# motor_drive.net
KiCad netlist of a schematic drawn in Altium Designer
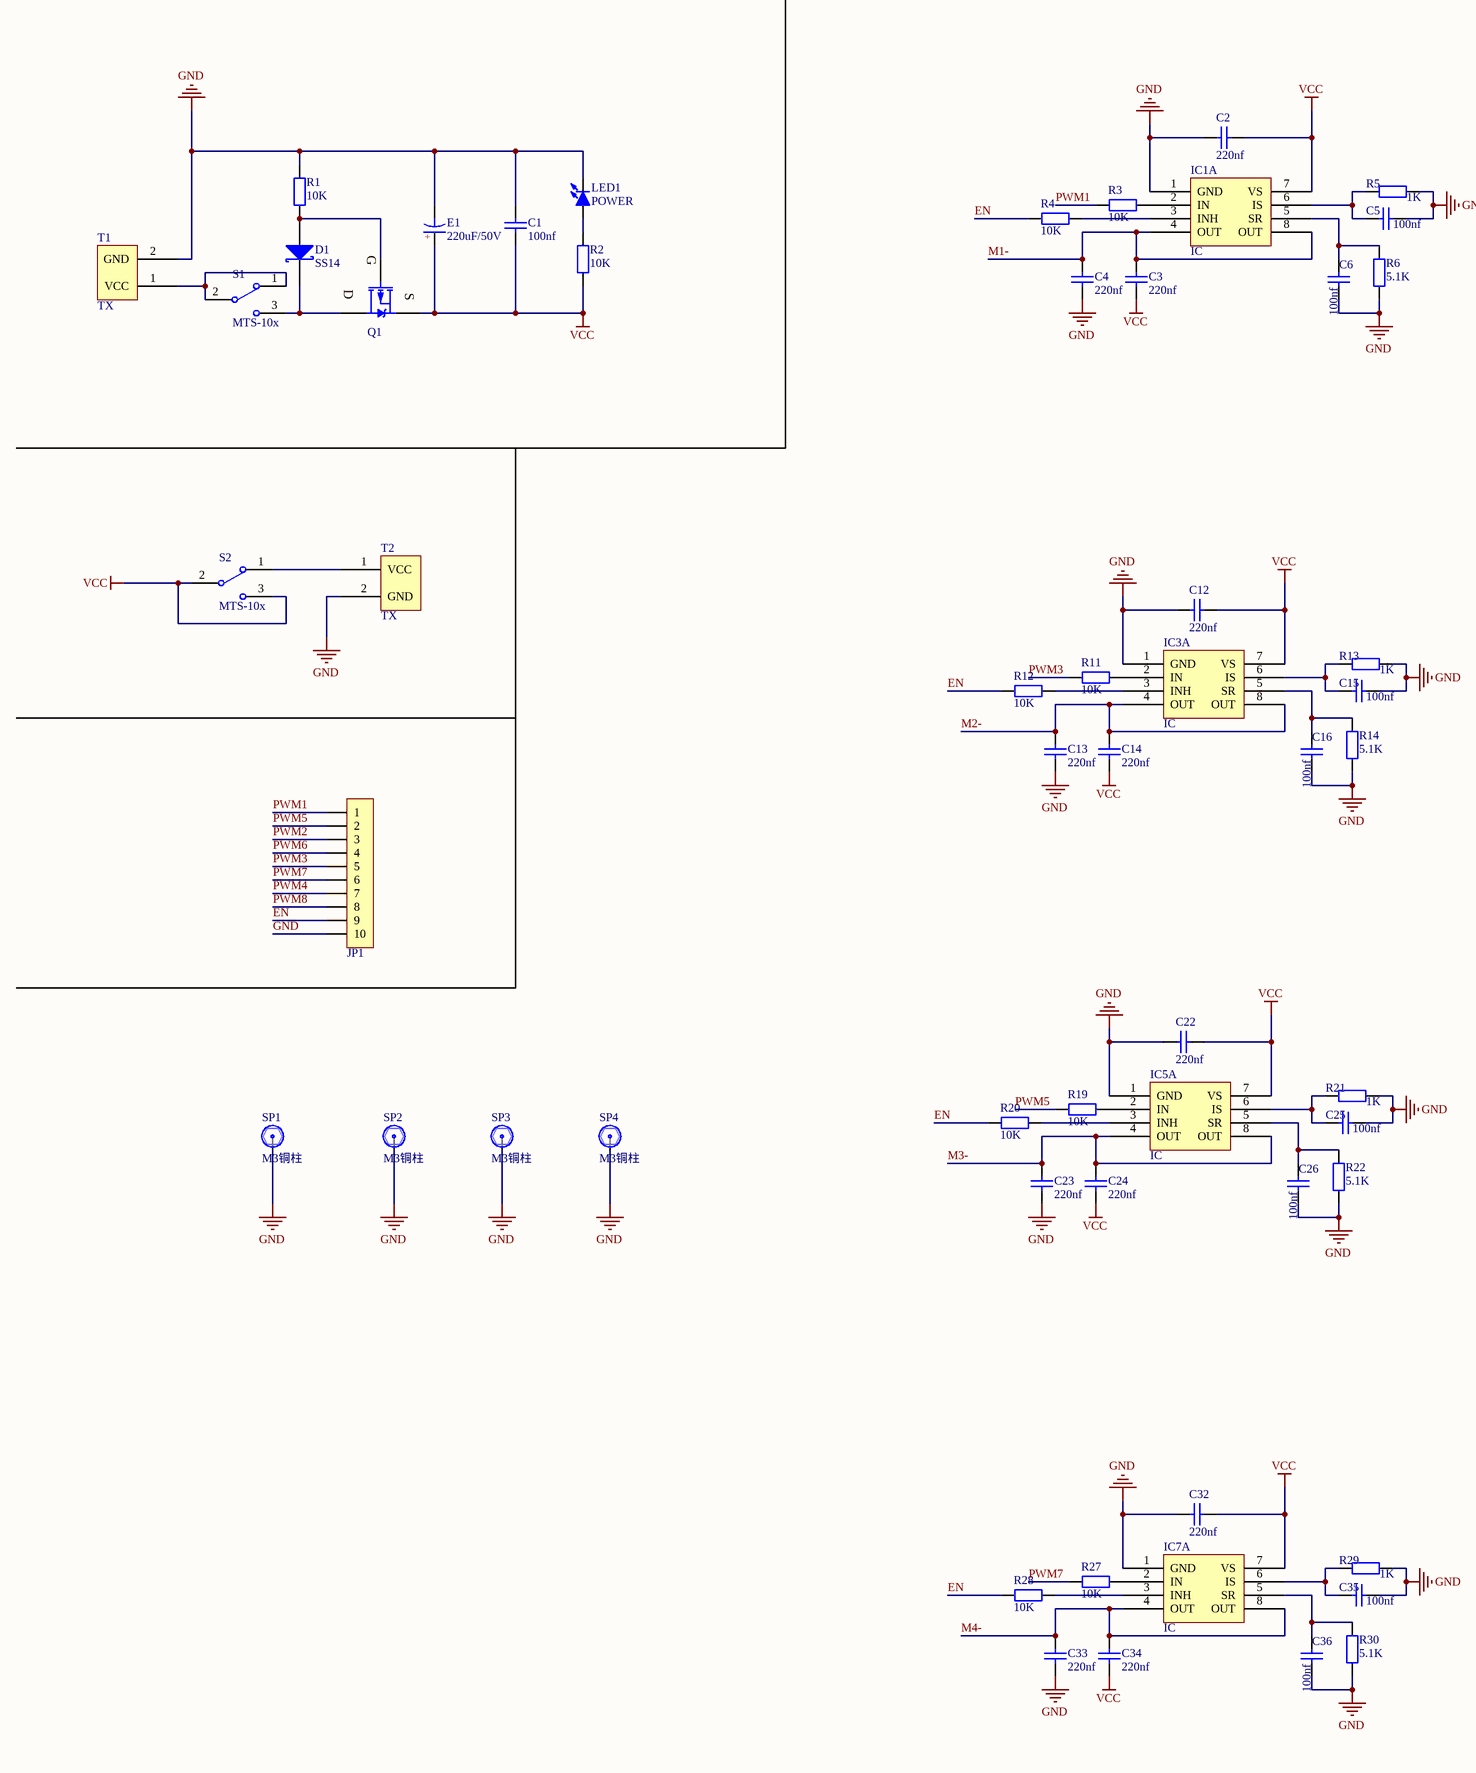
[diagram p0: motor_drive.SchDoc, left]
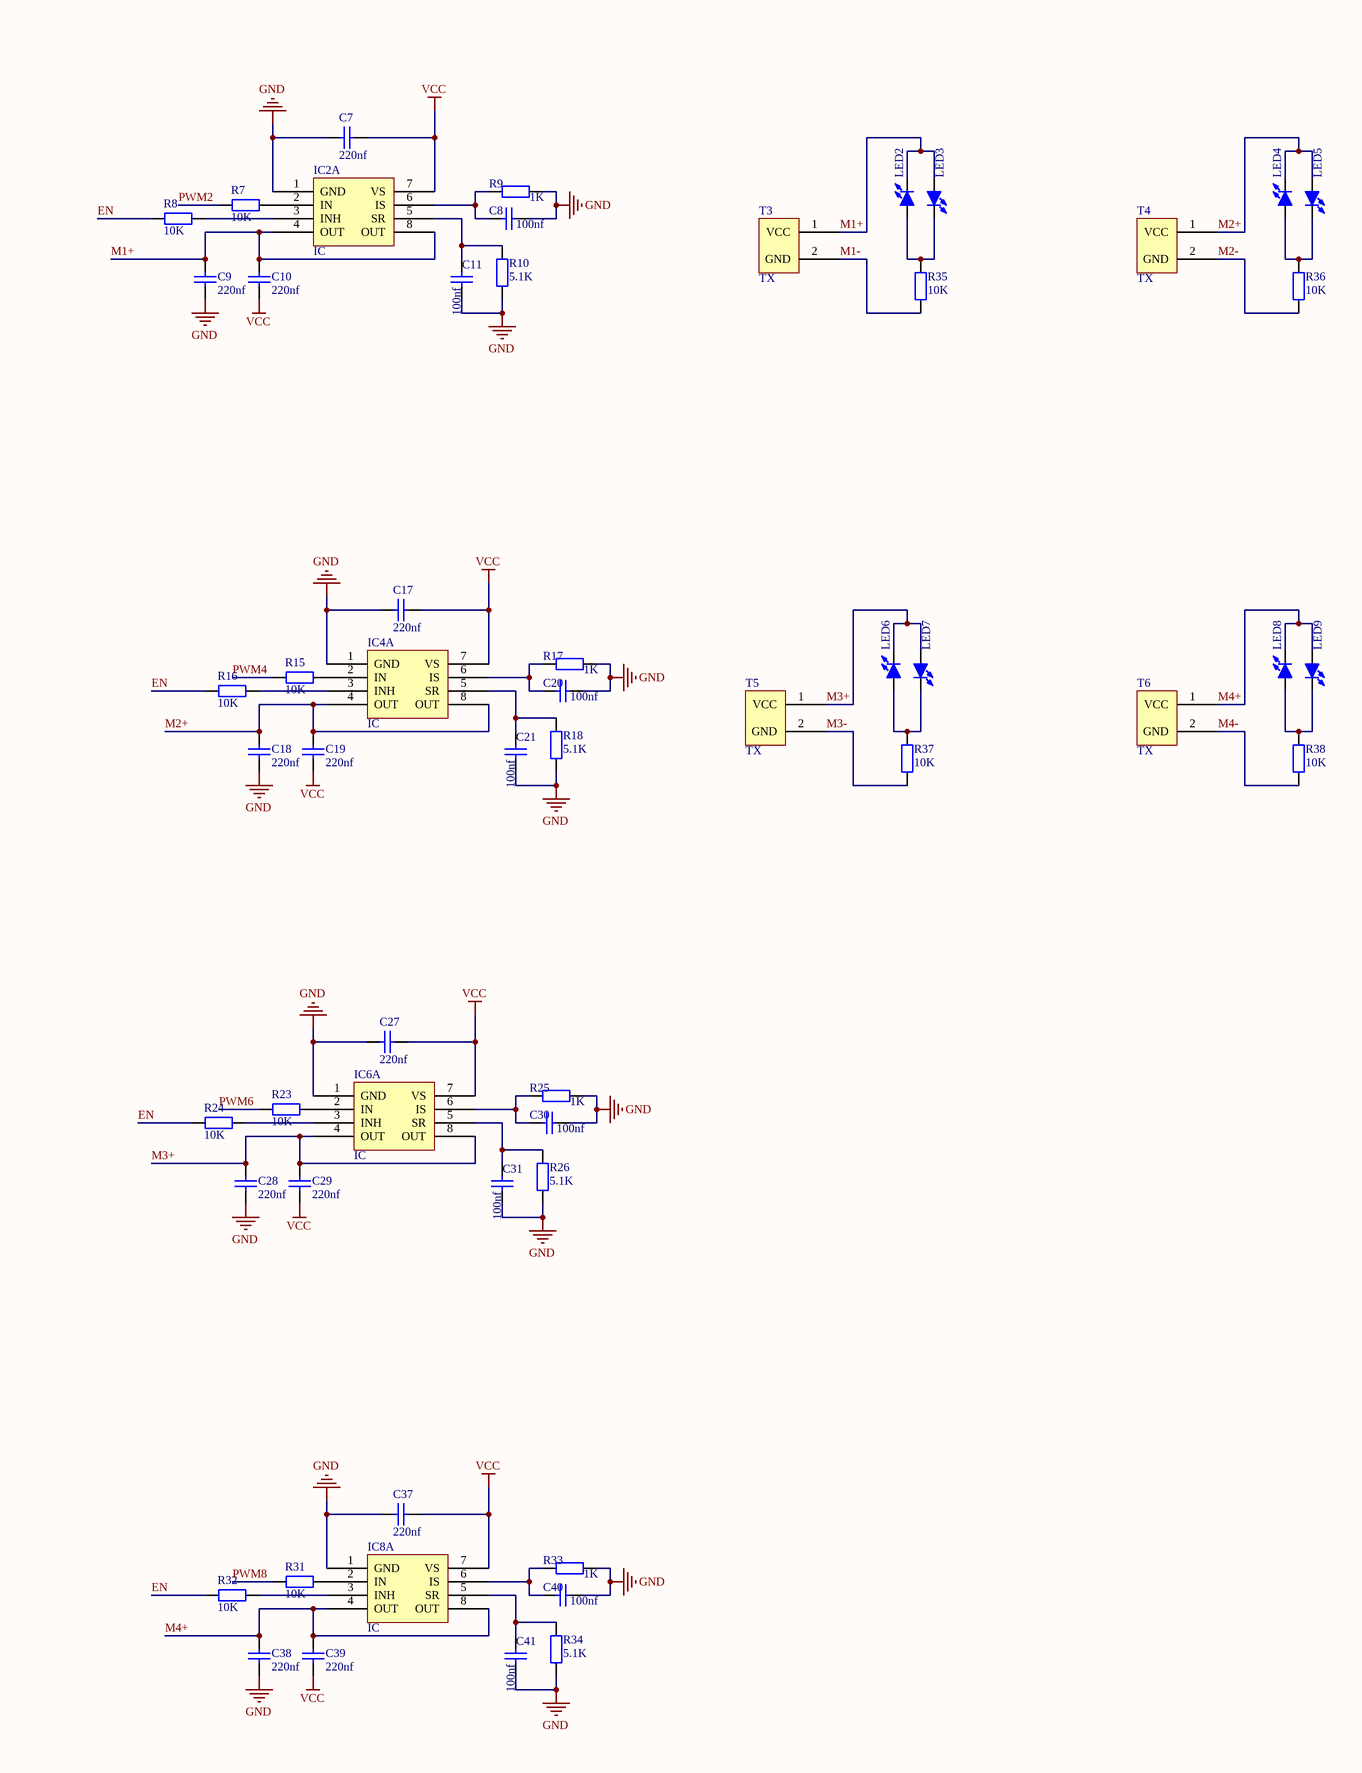
[diagram p1: motor_drive.SchDoc, right]

(export (version "E")
  (design (tool "Eeschema 10.0.6"))
  (components
    (comp (ref "C1")
      (value "100nf")
      (footprint "C0805_L")
      (description "贴片电容/MLCC电容")
      (libsource (lib "0.1 - 电阻-电容-电感-晶振-晶体-磁珠-电位器-法拉电容-馈通电容") (part "C"))
    )
    (comp (ref "C2")
      (value "220nf")
      (footprint "C0805_L")
      (description "贴片电容/MLCC电容")
      (libsource (lib "0.1 - 电阻-电容-电感-晶振-晶体-磁珠-电位器-法拉电容-馈通电容") (part "C"))
    )
    (comp (ref "C3")
      (value "220nf")
      (footprint "C0805_L")
      (description "贴片电容/MLCC电容")
      (libsource (lib "0.1 - 电阻-电容-电感-晶振-晶体-磁珠-电位器-法拉电容-馈通电容") (part "C"))
    )
    (comp (ref "C4")
      (value "220nf")
      (footprint "C0805_L")
      (description "贴片电容/MLCC电容")
      (libsource (lib "0.1 - 电阻-电容-电感-晶振-晶体-磁珠-电位器-法拉电容-馈通电容") (part "C"))
    )
    (comp (ref "C5")
      (value "100nf")
      (footprint "C0805_L")
      (description "贴片电容/MLCC电容")
      (libsource (lib "0.1 - 电阻-电容-电感-晶振-晶体-磁珠-电位器-法拉电容-馈通电容") (part "C"))
    )
    (comp (ref "C6")
      (value "100nf")
      (footprint "C0805_L")
      (description "贴片电容/MLCC电容")
      (libsource (lib "0.1 - 电阻-电容-电感-晶振-晶体-磁珠-电位器-法拉电容-馈通电容") (part "C"))
    )
    (comp (ref "C7")
      (value "220nf")
      (footprint "C0805_L")
      (description "贴片电容/MLCC电容")
      (libsource (lib "0.1 - 电阻-电容-电感-晶振-晶体-磁珠-电位器-法拉电容-馈通电容") (part "C"))
    )
    (comp (ref "C8")
      (value "100nf")
      (footprint "C0805_L")
      (description "贴片电容/MLCC电容")
      (libsource (lib "0.1 - 电阻-电容-电感-晶振-晶体-磁珠-电位器-法拉电容-馈通电容") (part "C"))
    )
    (comp (ref "C9")
      (value "220nf")
      (footprint "C0805_L")
      (description "贴片电容/MLCC电容")
      (libsource (lib "0.1 - 电阻-电容-电感-晶振-晶体-磁珠-电位器-法拉电容-馈通电容") (part "C"))
    )
    (comp (ref "C10")
      (value "220nf")
      (footprint "C0805_L")
      (description "贴片电容/MLCC电容")
      (libsource (lib "0.1 - 电阻-电容-电感-晶振-晶体-磁珠-电位器-法拉电容-馈通电容") (part "C"))
    )
    (comp (ref "C11")
      (value "100nf")
      (footprint "C0805_L")
      (description "贴片电容/MLCC电容")
      (libsource (lib "0.1 - 电阻-电容-电感-晶振-晶体-磁珠-电位器-法拉电容-馈通电容") (part "C"))
    )
    (comp (ref "C12")
      (value "220nf")
      (footprint "C0805_L")
      (description "贴片电容/MLCC电容")
      (libsource (lib "0.1 - 电阻-电容-电感-晶振-晶体-磁珠-电位器-法拉电容-馈通电容") (part "C"))
    )
    (comp (ref "C13")
      (value "220nf")
      (footprint "C0805_L")
      (description "贴片电容/MLCC电容")
      (libsource (lib "0.1 - 电阻-电容-电感-晶振-晶体-磁珠-电位器-法拉电容-馈通电容") (part "C"))
    )
    (comp (ref "C14")
      (value "220nf")
      (footprint "C0805_L")
      (description "贴片电容/MLCC电容")
      (libsource (lib "0.1 - 电阻-电容-电感-晶振-晶体-磁珠-电位器-法拉电容-馈通电容") (part "C"))
    )
    (comp (ref "C15")
      (value "100nf")
      (footprint "C0805_L")
      (description "贴片电容/MLCC电容")
      (libsource (lib "0.1 - 电阻-电容-电感-晶振-晶体-磁珠-电位器-法拉电容-馈通电容") (part "C"))
    )
    (comp (ref "C16")
      (value "100nf")
      (footprint "C0805_L")
      (description "贴片电容/MLCC电容")
      (libsource (lib "0.1 - 电阻-电容-电感-晶振-晶体-磁珠-电位器-法拉电容-馈通电容") (part "C"))
    )
    (comp (ref "C17")
      (value "220nf")
      (footprint "C0805_L")
      (description "贴片电容/MLCC电容")
      (libsource (lib "0.1 - 电阻-电容-电感-晶振-晶体-磁珠-电位器-法拉电容-馈通电容") (part "C"))
    )
    (comp (ref "C18")
      (value "220nf")
      (footprint "C0805_L")
      (description "贴片电容/MLCC电容")
      (libsource (lib "0.1 - 电阻-电容-电感-晶振-晶体-磁珠-电位器-法拉电容-馈通电容") (part "C"))
    )
    (comp (ref "C19")
      (value "220nf")
      (footprint "C0805_L")
      (description "贴片电容/MLCC电容")
      (libsource (lib "0.1 - 电阻-电容-电感-晶振-晶体-磁珠-电位器-法拉电容-馈通电容") (part "C"))
    )
    (comp (ref "C20")
      (value "100nf")
      (footprint "C0805_L")
      (description "贴片电容/MLCC电容")
      (libsource (lib "0.1 - 电阻-电容-电感-晶振-晶体-磁珠-电位器-法拉电容-馈通电容") (part "C"))
    )
    (comp (ref "C21")
      (value "100nf")
      (footprint "C0805_L")
      (description "贴片电容/MLCC电容")
      (libsource (lib "0.1 - 电阻-电容-电感-晶振-晶体-磁珠-电位器-法拉电容-馈通电容") (part "C"))
    )
    (comp (ref "C22")
      (value "220nf")
      (footprint "C0805_L")
      (description "贴片电容/MLCC电容")
      (libsource (lib "0.1 - 电阻-电容-电感-晶振-晶体-磁珠-电位器-法拉电容-馈通电容") (part "C"))
    )
    (comp (ref "C23")
      (value "220nf")
      (footprint "C0805_L")
      (description "贴片电容/MLCC电容")
      (libsource (lib "0.1 - 电阻-电容-电感-晶振-晶体-磁珠-电位器-法拉电容-馈通电容") (part "C"))
    )
    (comp (ref "C24")
      (value "220nf")
      (footprint "C0805_L")
      (description "贴片电容/MLCC电容")
      (libsource (lib "0.1 - 电阻-电容-电感-晶振-晶体-磁珠-电位器-法拉电容-馈通电容") (part "C"))
    )
    (comp (ref "C25")
      (value "100nf")
      (footprint "C0805_L")
      (description "贴片电容/MLCC电容")
      (libsource (lib "0.1 - 电阻-电容-电感-晶振-晶体-磁珠-电位器-法拉电容-馈通电容") (part "C"))
    )
    (comp (ref "C26")
      (value "100nf")
      (footprint "C0805_L")
      (description "贴片电容/MLCC电容")
      (libsource (lib "0.1 - 电阻-电容-电感-晶振-晶体-磁珠-电位器-法拉电容-馈通电容") (part "C"))
    )
    (comp (ref "C27")
      (value "220nf")
      (footprint "C0805_L")
      (description "贴片电容/MLCC电容")
      (libsource (lib "0.1 - 电阻-电容-电感-晶振-晶体-磁珠-电位器-法拉电容-馈通电容") (part "C"))
    )
    (comp (ref "C28")
      (value "220nf")
      (footprint "C0805_L")
      (description "贴片电容/MLCC电容")
      (libsource (lib "0.1 - 电阻-电容-电感-晶振-晶体-磁珠-电位器-法拉电容-馈通电容") (part "C"))
    )
    (comp (ref "C29")
      (value "220nf")
      (footprint "C0805_L")
      (description "贴片电容/MLCC电容")
      (libsource (lib "0.1 - 电阻-电容-电感-晶振-晶体-磁珠-电位器-法拉电容-馈通电容") (part "C"))
    )
    (comp (ref "C30")
      (value "100nf")
      (footprint "C0805_L")
      (description "贴片电容/MLCC电容")
      (libsource (lib "0.1 - 电阻-电容-电感-晶振-晶体-磁珠-电位器-法拉电容-馈通电容") (part "C"))
    )
    (comp (ref "C31")
      (value "100nf")
      (footprint "C0805_L")
      (description "贴片电容/MLCC电容")
      (libsource (lib "0.1 - 电阻-电容-电感-晶振-晶体-磁珠-电位器-法拉电容-馈通电容") (part "C"))
    )
    (comp (ref "C32")
      (value "220nf")
      (footprint "C0805_L")
      (description "贴片电容/MLCC电容")
      (libsource (lib "0.1 - 电阻-电容-电感-晶振-晶体-磁珠-电位器-法拉电容-馈通电容") (part "C"))
    )
    (comp (ref "C33")
      (value "220nf")
      (footprint "C0805_L")
      (description "贴片电容/MLCC电容")
      (libsource (lib "0.1 - 电阻-电容-电感-晶振-晶体-磁珠-电位器-法拉电容-馈通电容") (part "C"))
    )
    (comp (ref "C34")
      (value "220nf")
      (footprint "C0805_L")
      (description "贴片电容/MLCC电容")
      (libsource (lib "0.1 - 电阻-电容-电感-晶振-晶体-磁珠-电位器-法拉电容-馈通电容") (part "C"))
    )
    (comp (ref "C35")
      (value "100nf")
      (footprint "C0805_L")
      (description "贴片电容/MLCC电容")
      (libsource (lib "0.1 - 电阻-电容-电感-晶振-晶体-磁珠-电位器-法拉电容-馈通电容") (part "C"))
    )
    (comp (ref "C36")
      (value "100nf")
      (footprint "C0805_L")
      (description "贴片电容/MLCC电容")
      (libsource (lib "0.1 - 电阻-电容-电感-晶振-晶体-磁珠-电位器-法拉电容-馈通电容") (part "C"))
    )
    (comp (ref "C37")
      (value "220nf")
      (footprint "C0805_L")
      (description "贴片电容/MLCC电容")
      (libsource (lib "0.1 - 电阻-电容-电感-晶振-晶体-磁珠-电位器-法拉电容-馈通电容") (part "C"))
    )
    (comp (ref "C38")
      (value "220nf")
      (footprint "C0805_L")
      (description "贴片电容/MLCC电容")
      (libsource (lib "0.1 - 电阻-电容-电感-晶振-晶体-磁珠-电位器-法拉电容-馈通电容") (part "C"))
    )
    (comp (ref "C39")
      (value "220nf")
      (footprint "C0805_L")
      (description "贴片电容/MLCC电容")
      (libsource (lib "0.1 - 电阻-电容-电感-晶振-晶体-磁珠-电位器-法拉电容-馈通电容") (part "C"))
    )
    (comp (ref "C40")
      (value "100nf")
      (footprint "C0805_L")
      (description "贴片电容/MLCC电容")
      (libsource (lib "0.1 - 电阻-电容-电感-晶振-晶体-磁珠-电位器-法拉电容-馈通电容") (part "C"))
    )
    (comp (ref "C41")
      (value "100nf")
      (footprint "C0805_L")
      (description "贴片电容/MLCC电容")
      (libsource (lib "0.1 - 电阻-电容-电感-晶振-晶体-磁珠-电位器-法拉电容-馈通电容") (part "C"))
    )
    (comp (ref "D1")
      (value "SS14")
      (footprint "SMA")
      (description "肖特基二极管")
      (libsource (lib "0.2 - 二极管-TVS-ESD-整流桥-放电管") (part "SS14"))
    )
    (comp (ref "E1")
      (value "220uF/50V")
      (footprint "CE F(10*10.2)")
      (description "贴片电解电容")
      (libsource (lib "0.1 - 电阻-电容-电感-晶振-晶体-磁珠-电位器-法拉电容-馈通电容") (part "CE_SMD"))
    )
    (comp (ref "IC1") (value "IC") (libsource (lib "BTN8982") (part "BTN8982")))
    (comp (ref "IC2") (value "IC") (libsource (lib "BTN8982") (part "BTN8982")))
    (comp (ref "IC3") (value "IC") (libsource (lib "BTN8982") (part "BTN8982")))
    (comp (ref "IC4") (value "IC") (libsource (lib "BTN8982") (part "BTN8982")))
    (comp (ref "IC5") (value "IC") (libsource (lib "BTN8982") (part "BTN8982")))
    (comp (ref "IC6") (value "IC") (libsource (lib "BTN8982") (part "BTN8982")))
    (comp (ref "IC7") (value "IC") (libsource (lib "BTN8982") (part "BTN8982")))
    (comp (ref "IC8") (value "IC") (libsource (lib "BTN8982") (part "BTN8982")))
    (comp (ref "JP1")
      (value "HDR-1X10")
      (footprint "XH2.54-LI-10P")
      (description "10P接插件")
      (libsource (lib "5.5 - 2.54mm连接器(KF2EDGK_XH2.54_2.54排针排母)") (part "Header 10"))
    )
    (comp (ref "LED1")
      (value "POWER")
      (footprint "LED 0805R")
      (description "贴片LED")
      (fields (field (name "版权归属") "封装库来自淘宝 ID：黄晶宝石"))
      (libsource (lib "0.3 - LED发光二极管") (part "LED-SMD"))
    )
    (comp (ref "LED2")
      (value "~")
      (footprint "LED 0805R")
      (description "贴片LED")
      (fields (field (name "版权归属") "封装库来自淘宝 ID：黄晶宝石"))
      (libsource (lib "0.3 - LED发光二极管") (part "LED-SMD"))
    )
    (comp (ref "LED3")
      (value "~")
      (footprint "LED 0805R")
      (description "贴片LED")
      (fields (field (name "版权归属") "封装库来自淘宝 ID：黄晶宝石"))
      (libsource (lib "0.3 - LED发光二极管") (part "LED-SMD"))
    )
    (comp (ref "LED4")
      (value "~")
      (footprint "LED 0805R")
      (description "贴片LED")
      (fields (field (name "版权归属") "封装库来自淘宝 ID：黄晶宝石"))
      (libsource (lib "0.3 - LED发光二极管") (part "LED-SMD"))
    )
    (comp (ref "LED5")
      (value "~")
      (footprint "LED 0805R")
      (description "贴片LED")
      (fields (field (name "版权归属") "封装库来自淘宝 ID：黄晶宝石"))
      (libsource (lib "0.3 - LED发光二极管") (part "LED-SMD"))
    )
    (comp (ref "LED6")
      (value "~")
      (footprint "LED 0805R")
      (description "贴片LED")
      (fields (field (name "版权归属") "封装库来自淘宝 ID：黄晶宝石"))
      (libsource (lib "0.3 - LED发光二极管") (part "LED-SMD"))
    )
    (comp (ref "LED7")
      (value "~")
      (footprint "LED 0805R")
      (description "贴片LED")
      (fields (field (name "版权归属") "封装库来自淘宝 ID：黄晶宝石"))
      (libsource (lib "0.3 - LED发光二极管") (part "LED-SMD"))
    )
    (comp (ref "LED8")
      (value "~")
      (footprint "LED 0805R")
      (description "贴片LED")
      (fields (field (name "版权归属") "封装库来自淘宝 ID：黄晶宝石"))
      (libsource (lib "0.3 - LED发光二极管") (part "LED-SMD"))
    )
    (comp (ref "LED9")
      (value "~")
      (footprint "LED 0805R")
      (description "贴片LED")
      (fields (field (name "版权归属") "封装库来自淘宝 ID：黄晶宝石"))
      (libsource (lib "0.3 - LED发光二极管") (part "LED-SMD"))
    )
    (comp (ref "Q1")
      (value "D15P05")
      (footprint "TO252")
      (description "P沟道 50V/15A")
      (libsource (lib "0.4 - 三极管-场效应管-可控硅") (part "D15P05"))
    )
    (comp (ref "R1")
      (value "10K")
      (footprint "R0805_L")
      (description "贴片电阻")
      (libsource (lib "0.1 - 电阻-电容-电感-晶振-晶体-磁珠-电位器-法拉电容-馈通电容") (part "R"))
    )
    (comp (ref "R2")
      (value "10K")
      (footprint "R0805_L")
      (description "贴片电阻")
      (libsource (lib "0.1 - 电阻-电容-电感-晶振-晶体-磁珠-电位器-法拉电容-馈通电容") (part "R"))
    )
    (comp (ref "R3")
      (value "10K")
      (footprint "R0805_L")
      (description "贴片电阻")
      (libsource (lib "0.1 - 电阻-电容-电感-晶振-晶体-磁珠-电位器-法拉电容-馈通电容") (part "R"))
    )
    (comp (ref "R4")
      (value "10K")
      (footprint "R0805_L")
      (description "贴片电阻")
      (libsource (lib "0.1 - 电阻-电容-电感-晶振-晶体-磁珠-电位器-法拉电容-馈通电容") (part "R"))
    )
    (comp (ref "R5")
      (value "1K")
      (footprint "R0805_L")
      (description "贴片电阻")
      (libsource (lib "0.1 - 电阻-电容-电感-晶振-晶体-磁珠-电位器-法拉电容-馈通电容") (part "R"))
    )
    (comp (ref "R6")
      (value "5.1K")
      (footprint "R0805_L")
      (description "贴片电阻")
      (libsource (lib "0.1 - 电阻-电容-电感-晶振-晶体-磁珠-电位器-法拉电容-馈通电容") (part "R"))
    )
    (comp (ref "R7")
      (value "10K")
      (footprint "R0805_L")
      (description "贴片电阻")
      (libsource (lib "0.1 - 电阻-电容-电感-晶振-晶体-磁珠-电位器-法拉电容-馈通电容") (part "R"))
    )
    (comp (ref "R8")
      (value "10K")
      (footprint "R0805_L")
      (description "贴片电阻")
      (libsource (lib "0.1 - 电阻-电容-电感-晶振-晶体-磁珠-电位器-法拉电容-馈通电容") (part "R"))
    )
    (comp (ref "R9")
      (value "1K")
      (footprint "R0805_L")
      (description "贴片电阻")
      (libsource (lib "0.1 - 电阻-电容-电感-晶振-晶体-磁珠-电位器-法拉电容-馈通电容") (part "R"))
    )
    (comp (ref "R10")
      (value "5.1K")
      (footprint "R0805_L")
      (description "贴片电阻")
      (libsource (lib "0.1 - 电阻-电容-电感-晶振-晶体-磁珠-电位器-法拉电容-馈通电容") (part "R"))
    )
    (comp (ref "R11")
      (value "10K")
      (footprint "R0805_L")
      (description "贴片电阻")
      (libsource (lib "0.1 - 电阻-电容-电感-晶振-晶体-磁珠-电位器-法拉电容-馈通电容") (part "R"))
    )
    (comp (ref "R12")
      (value "10K")
      (footprint "R0805_L")
      (description "贴片电阻")
      (libsource (lib "0.1 - 电阻-电容-电感-晶振-晶体-磁珠-电位器-法拉电容-馈通电容") (part "R"))
    )
    (comp (ref "R13")
      (value "1K")
      (footprint "R0805_L")
      (description "贴片电阻")
      (libsource (lib "0.1 - 电阻-电容-电感-晶振-晶体-磁珠-电位器-法拉电容-馈通电容") (part "R"))
    )
    (comp (ref "R14")
      (value "5.1K")
      (footprint "R0805_L")
      (description "贴片电阻")
      (libsource (lib "0.1 - 电阻-电容-电感-晶振-晶体-磁珠-电位器-法拉电容-馈通电容") (part "R"))
    )
    (comp (ref "R15")
      (value "10K")
      (footprint "R0805_L")
      (description "贴片电阻")
      (libsource (lib "0.1 - 电阻-电容-电感-晶振-晶体-磁珠-电位器-法拉电容-馈通电容") (part "R"))
    )
    (comp (ref "R16")
      (value "10K")
      (footprint "R0805_L")
      (description "贴片电阻")
      (libsource (lib "0.1 - 电阻-电容-电感-晶振-晶体-磁珠-电位器-法拉电容-馈通电容") (part "R"))
    )
    (comp (ref "R17")
      (value "1K")
      (footprint "R0805_L")
      (description "贴片电阻")
      (libsource (lib "0.1 - 电阻-电容-电感-晶振-晶体-磁珠-电位器-法拉电容-馈通电容") (part "R"))
    )
    (comp (ref "R18")
      (value "5.1K")
      (footprint "R0805_L")
      (description "贴片电阻")
      (libsource (lib "0.1 - 电阻-电容-电感-晶振-晶体-磁珠-电位器-法拉电容-馈通电容") (part "R"))
    )
    (comp (ref "R19")
      (value "10K")
      (footprint "R0805_L")
      (description "贴片电阻")
      (libsource (lib "0.1 - 电阻-电容-电感-晶振-晶体-磁珠-电位器-法拉电容-馈通电容") (part "R"))
    )
    (comp (ref "R20")
      (value "10K")
      (footprint "R0805_L")
      (description "贴片电阻")
      (libsource (lib "0.1 - 电阻-电容-电感-晶振-晶体-磁珠-电位器-法拉电容-馈通电容") (part "R"))
    )
    (comp (ref "R21")
      (value "1K")
      (footprint "R0805_L")
      (description "贴片电阻")
      (libsource (lib "0.1 - 电阻-电容-电感-晶振-晶体-磁珠-电位器-法拉电容-馈通电容") (part "R"))
    )
    (comp (ref "R22")
      (value "5.1K")
      (footprint "R0805_L")
      (description "贴片电阻")
      (libsource (lib "0.1 - 电阻-电容-电感-晶振-晶体-磁珠-电位器-法拉电容-馈通电容") (part "R"))
    )
    (comp (ref "R23")
      (value "10K")
      (footprint "R0805_L")
      (description "贴片电阻")
      (libsource (lib "0.1 - 电阻-电容-电感-晶振-晶体-磁珠-电位器-法拉电容-馈通电容") (part "R"))
    )
    (comp (ref "R24")
      (value "10K")
      (footprint "R0805_L")
      (description "贴片电阻")
      (libsource (lib "0.1 - 电阻-电容-电感-晶振-晶体-磁珠-电位器-法拉电容-馈通电容") (part "R"))
    )
    (comp (ref "R25")
      (value "1K")
      (footprint "R0805_L")
      (description "贴片电阻")
      (libsource (lib "0.1 - 电阻-电容-电感-晶振-晶体-磁珠-电位器-法拉电容-馈通电容") (part "R"))
    )
    (comp (ref "R26")
      (value "5.1K")
      (footprint "R0805_L")
      (description "贴片电阻")
      (libsource (lib "0.1 - 电阻-电容-电感-晶振-晶体-磁珠-电位器-法拉电容-馈通电容") (part "R"))
    )
    (comp (ref "R27")
      (value "10K")
      (footprint "R0805_L")
      (description "贴片电阻")
      (libsource (lib "0.1 - 电阻-电容-电感-晶振-晶体-磁珠-电位器-法拉电容-馈通电容") (part "R"))
    )
    (comp (ref "R28")
      (value "10K")
      (footprint "R0805_L")
      (description "贴片电阻")
      (libsource (lib "0.1 - 电阻-电容-电感-晶振-晶体-磁珠-电位器-法拉电容-馈通电容") (part "R"))
    )
    (comp (ref "R29")
      (value "1K")
      (footprint "R0805_L")
      (description "贴片电阻")
      (libsource (lib "0.1 - 电阻-电容-电感-晶振-晶体-磁珠-电位器-法拉电容-馈通电容") (part "R"))
    )
    (comp (ref "R30")
      (value "5.1K")
      (footprint "R0805_L")
      (description "贴片电阻")
      (libsource (lib "0.1 - 电阻-电容-电感-晶振-晶体-磁珠-电位器-法拉电容-馈通电容") (part "R"))
    )
    (comp (ref "R31")
      (value "10K")
      (footprint "R0805_L")
      (description "贴片电阻")
      (libsource (lib "0.1 - 电阻-电容-电感-晶振-晶体-磁珠-电位器-法拉电容-馈通电容") (part "R"))
    )
    (comp (ref "R32")
      (value "10K")
      (footprint "R0805_L")
      (description "贴片电阻")
      (libsource (lib "0.1 - 电阻-电容-电感-晶振-晶体-磁珠-电位器-法拉电容-馈通电容") (part "R"))
    )
    (comp (ref "R33")
      (value "1K")
      (footprint "R0805_L")
      (description "贴片电阻")
      (libsource (lib "0.1 - 电阻-电容-电感-晶振-晶体-磁珠-电位器-法拉电容-馈通电容") (part "R"))
    )
    (comp (ref "R34")
      (value "5.1K")
      (footprint "R0805_L")
      (description "贴片电阻")
      (libsource (lib "0.1 - 电阻-电容-电感-晶振-晶体-磁珠-电位器-法拉电容-馈通电容") (part "R"))
    )
    (comp (ref "R35")
      (value "10K")
      (footprint "R0805_L")
      (description "贴片电阻")
      (libsource (lib "0.1 - 电阻-电容-电感-晶振-晶体-磁珠-电位器-法拉电容-馈通电容") (part "R"))
    )
    (comp (ref "R36")
      (value "10K")
      (footprint "R0805_L")
      (description "贴片电阻")
      (libsource (lib "0.1 - 电阻-电容-电感-晶振-晶体-磁珠-电位器-法拉电容-馈通电容") (part "R"))
    )
    (comp (ref "R37")
      (value "10K")
      (footprint "R0805_L")
      (description "贴片电阻")
      (libsource (lib "0.1 - 电阻-电容-电感-晶振-晶体-磁珠-电位器-法拉电容-馈通电容") (part "R"))
    )
    (comp (ref "R38")
      (value "10K")
      (footprint "R0805_L")
      (description "贴片电阻")
      (libsource (lib "0.1 - 电阻-电容-电感-晶振-晶体-磁珠-电位器-法拉电容-馈通电容") (part "R"))
    )
    (comp (ref "S1")
      (value "MTS-10x")
      (footprint "MTS-10x")
      (description "MTS10x系列3脚扭子开关")
      (libsource (lib "0.5 - 按键_开关_蜂鸣器_保险丝_电池_测试点_Mark点_铜柱") (part "MTS-10x"))
    )
    (comp (ref "S2")
      (value "MTS-10x")
      (footprint "MTS-10x")
      (description "MTS10x系列3脚扭子开关")
      (libsource (lib "0.5 - 按键_开关_蜂鸣器_保险丝_电池_测试点_Mark点_铜柱") (part "MTS-10x"))
    )
    (comp (ref "SP1")
      (value "M3铜柱")
      (footprint "M3x4+6_N")
      (description "铜柱")
      (libsource (lib "0.5 - 按键_开关_蜂鸣器_保险丝_电池_测试点_Mark点_铜柱") (part "铜柱加头大焊盘"))
    )
    (comp (ref "SP2")
      (value "M3铜柱")
      (footprint "M3x4+6_N")
      (description "铜柱")
      (libsource (lib "0.5 - 按键_开关_蜂鸣器_保险丝_电池_测试点_Mark点_铜柱") (part "铜柱加头大焊盘"))
    )
    (comp (ref "SP3")
      (value "M3铜柱")
      (footprint "M3x4+6_N")
      (description "铜柱")
      (libsource (lib "0.5 - 按键_开关_蜂鸣器_保险丝_电池_测试点_Mark点_铜柱") (part "铜柱加头大焊盘"))
    )
    (comp (ref "SP4")
      (value "M3铜柱")
      (footprint "M3x4+6_N")
      (description "铜柱")
      (libsource (lib "0.5 - 按键_开关_蜂鸣器_保险丝_电池_测试点_Mark点_铜柱") (part "铜柱加头大焊盘"))
    )
    (comp (ref "T1") (value "TX") (footprint "T接头") (libsource (lib "") (part "T接头_2")))
    (comp (ref "T2") (value "TX") (footprint "T接头") (libsource (lib "") (part "T接头_1")))
    (comp (ref "T3") (value "TX") (footprint "T接头") (libsource (lib "T接头") (part "T接头")))
    (comp (ref "T4") (value "TX") (footprint "T接头") (libsource (lib "T接头") (part "T接头")))
    (comp (ref "T5") (value "TX") (footprint "T接头") (libsource (lib "T接头") (part "T接头")))
    (comp (ref "T6") (value "TX") (footprint "T接头") (libsource (lib "T接头") (part "T接头")))
  )
  (nets
    (net (code "1") (name "/EN") (class "Default")
      (node (ref "JP1") (pin "9") (pinfunction "9_9") (pintype "passive"))
      (node (ref "R12") (pin "1") (pinfunction "1_1") (pintype "passive"))
      (node (ref "R16") (pin "1") (pinfunction "1_1") (pintype "passive"))
      (node (ref "R20") (pin "1") (pinfunction "1_1") (pintype "passive"))
      (node (ref "R24") (pin "1") (pinfunction "1_1") (pintype "passive"))
      (node (ref "R28") (pin "1") (pinfunction "1_1") (pintype "passive"))
      (node (ref "R32") (pin "1") (pinfunction "1_1") (pintype "passive"))
      (node (ref "R4") (pin "1") (pinfunction "1_1") (pintype "passive"))
      (node (ref "R8") (pin "1") (pinfunction "1_1") (pintype "passive"))
    )
    (net (code "2") (name "/M1+") (class "Default")
      (node (ref "C10") (pin "1") (pinfunction "1_1") (pintype "passive"))
      (node (ref "C9") (pin "1") (pinfunction "1_1") (pintype "passive"))
      (node (ref "IC2") (pin "4") (pinfunction "OUT_4") (pintype "passive"))
      (node (ref "IC2") (pin "8") (pinfunction "OUT_8") (pintype "passive"))
      (node (ref "LED2") (pin "2") (pinfunction "K_2") (pintype "passive"))
      (node (ref "LED3") (pin "1") (pinfunction "A_1") (pintype "passive"))
      (node (ref "T3") (pin "1") (pinfunction "VCC_1") (pintype "passive"))
    )
    (net (code "3") (name "/M1-") (class "Default")
      (node (ref "C3") (pin "1") (pinfunction "1_1") (pintype "passive"))
      (node (ref "C4") (pin "1") (pinfunction "1_1") (pintype "passive"))
      (node (ref "IC1") (pin "4") (pinfunction "OUT_4") (pintype "passive"))
      (node (ref "IC1") (pin "8") (pinfunction "OUT_8") (pintype "passive"))
      (node (ref "R35") (pin "1") (pinfunction "1_1") (pintype "passive"))
      (node (ref "T3") (pin "2") (pinfunction "GND_2") (pintype "passive"))
    )
    (net (code "4") (name "/M2+") (class "Default")
      (node (ref "C18") (pin "1") (pinfunction "1_1") (pintype "passive"))
      (node (ref "C19") (pin "1") (pinfunction "1_1") (pintype "passive"))
      (node (ref "IC4") (pin "4") (pinfunction "OUT_4") (pintype "passive"))
      (node (ref "IC4") (pin "8") (pinfunction "OUT_8") (pintype "passive"))
      (node (ref "LED4") (pin "2") (pinfunction "K_2") (pintype "passive"))
      (node (ref "LED5") (pin "1") (pinfunction "A_1") (pintype "passive"))
      (node (ref "T4") (pin "1") (pinfunction "VCC_1") (pintype "passive"))
    )
    (net (code "5") (name "/M2-") (class "Default")
      (node (ref "C13") (pin "1") (pinfunction "1_1") (pintype "passive"))
      (node (ref "C14") (pin "1") (pinfunction "1_1") (pintype "passive"))
      (node (ref "IC3") (pin "4") (pinfunction "OUT_4") (pintype "passive"))
      (node (ref "IC3") (pin "8") (pinfunction "OUT_8") (pintype "passive"))
      (node (ref "R36") (pin "1") (pinfunction "1_1") (pintype "passive"))
      (node (ref "T4") (pin "2") (pinfunction "GND_2") (pintype "passive"))
    )
    (net (code "6") (name "/M3+") (class "Default")
      (node (ref "C28") (pin "1") (pinfunction "1_1") (pintype "passive"))
      (node (ref "C29") (pin "1") (pinfunction "1_1") (pintype "passive"))
      (node (ref "IC6") (pin "4") (pinfunction "OUT_4") (pintype "passive"))
      (node (ref "IC6") (pin "8") (pinfunction "OUT_8") (pintype "passive"))
      (node (ref "LED6") (pin "2") (pinfunction "K_2") (pintype "passive"))
      (node (ref "LED7") (pin "1") (pinfunction "A_1") (pintype "passive"))
      (node (ref "T5") (pin "1") (pinfunction "VCC_1") (pintype "passive"))
    )
    (net (code "7") (name "/M3-") (class "Default")
      (node (ref "C23") (pin "1") (pinfunction "1_1") (pintype "passive"))
      (node (ref "C24") (pin "1") (pinfunction "1_1") (pintype "passive"))
      (node (ref "IC5") (pin "4") (pinfunction "OUT_4") (pintype "passive"))
      (node (ref "IC5") (pin "8") (pinfunction "OUT_8") (pintype "passive"))
      (node (ref "R37") (pin "1") (pinfunction "1_1") (pintype "passive"))
      (node (ref "T5") (pin "2") (pinfunction "GND_2") (pintype "passive"))
    )
    (net (code "8") (name "/M4+") (class "Default")
      (node (ref "C38") (pin "1") (pinfunction "1_1") (pintype "passive"))
      (node (ref "C39") (pin "1") (pinfunction "1_1") (pintype "passive"))
      (node (ref "IC8") (pin "4") (pinfunction "OUT_4") (pintype "passive"))
      (node (ref "IC8") (pin "8") (pinfunction "OUT_8") (pintype "passive"))
      (node (ref "LED8") (pin "2") (pinfunction "K_2") (pintype "passive"))
      (node (ref "LED9") (pin "1") (pinfunction "A_1") (pintype "passive"))
      (node (ref "T6") (pin "1") (pinfunction "VCC_1") (pintype "passive"))
    )
    (net (code "9") (name "/M4-") (class "Default")
      (node (ref "C33") (pin "1") (pinfunction "1_1") (pintype "passive"))
      (node (ref "C34") (pin "1") (pinfunction "1_1") (pintype "passive"))
      (node (ref "IC7") (pin "4") (pinfunction "OUT_4") (pintype "passive"))
      (node (ref "IC7") (pin "8") (pinfunction "OUT_8") (pintype "passive"))
      (node (ref "R38") (pin "1") (pinfunction "1_1") (pintype "passive"))
      (node (ref "T6") (pin "2") (pinfunction "GND_2") (pintype "passive"))
    )
    (net (code "10") (name "/PWM1") (class "Default")
      (node (ref "JP1") (pin "1") (pinfunction "1_1") (pintype "passive"))
      (node (ref "R3") (pin "1") (pinfunction "1_1") (pintype "passive"))
    )
    (net (code "11") (name "/PWM2") (class "Default")
      (node (ref "JP1") (pin "3") (pinfunction "3_3") (pintype "passive"))
      (node (ref "R7") (pin "1") (pinfunction "1_1") (pintype "passive"))
    )
    (net (code "12") (name "/PWM3") (class "Default")
      (node (ref "JP1") (pin "5") (pinfunction "5_5") (pintype "passive"))
      (node (ref "R11") (pin "1") (pinfunction "1_1") (pintype "passive"))
    )
    (net (code "13") (name "/PWM4") (class "Default")
      (node (ref "JP1") (pin "7") (pinfunction "7_7") (pintype "passive"))
      (node (ref "R15") (pin "1") (pinfunction "1_1") (pintype "passive"))
    )
    (net (code "14") (name "/PWM5") (class "Default")
      (node (ref "JP1") (pin "2") (pinfunction "2_2") (pintype "passive"))
      (node (ref "R19") (pin "1") (pinfunction "1_1") (pintype "passive"))
    )
    (net (code "15") (name "/PWM6") (class "Default")
      (node (ref "JP1") (pin "4") (pinfunction "4_4") (pintype "passive"))
      (node (ref "R23") (pin "1") (pinfunction "1_1") (pintype "passive"))
    )
    (net (code "16") (name "/PWM7") (class "Default")
      (node (ref "JP1") (pin "6") (pinfunction "6_6") (pintype "passive"))
      (node (ref "R27") (pin "1") (pinfunction "1_1") (pintype "passive"))
    )
    (net (code "17") (name "/PWM8") (class "Default")
      (node (ref "JP1") (pin "8") (pinfunction "8_8") (pintype "passive"))
      (node (ref "R31") (pin "1") (pinfunction "1_1") (pintype "passive"))
    )
    (net (code "18") (name "GND") (class "Default")
      (node (ref "C1") (pin "2") (pinfunction "2_2") (pintype "passive"))
      (node (ref "C11") (pin "1") (pinfunction "1_1") (pintype "passive"))
      (node (ref "C12") (pin "1") (pinfunction "1_1") (pintype "passive"))
      (node (ref "C13") (pin "2") (pinfunction "2_2") (pintype "passive"))
      (node (ref "C15") (pin "1") (pinfunction "1_1") (pintype "passive"))
      (node (ref "C16") (pin "1") (pinfunction "1_1") (pintype "passive"))
      (node (ref "C17") (pin "1") (pinfunction "1_1") (pintype "passive"))
      (node (ref "C18") (pin "2") (pinfunction "2_2") (pintype "passive"))
      (node (ref "C2") (pin "1") (pinfunction "1_1") (pintype "passive"))
      (node (ref "C20") (pin "1") (pinfunction "1_1") (pintype "passive"))
      (node (ref "C21") (pin "1") (pinfunction "1_1") (pintype "passive"))
      (node (ref "C22") (pin "1") (pinfunction "1_1") (pintype "passive"))
      (node (ref "C23") (pin "2") (pinfunction "2_2") (pintype "passive"))
      (node (ref "C25") (pin "1") (pinfunction "1_1") (pintype "passive"))
      (node (ref "C26") (pin "1") (pinfunction "1_1") (pintype "passive"))
      (node (ref "C27") (pin "1") (pinfunction "1_1") (pintype "passive"))
      (node (ref "C28") (pin "2") (pinfunction "2_2") (pintype "passive"))
      (node (ref "C30") (pin "1") (pinfunction "1_1") (pintype "passive"))
      (node (ref "C31") (pin "1") (pinfunction "1_1") (pintype "passive"))
      (node (ref "C32") (pin "1") (pinfunction "1_1") (pintype "passive"))
      (node (ref "C33") (pin "2") (pinfunction "2_2") (pintype "passive"))
      (node (ref "C35") (pin "1") (pinfunction "1_1") (pintype "passive"))
      (node (ref "C36") (pin "1") (pinfunction "1_1") (pintype "passive"))
      (node (ref "C37") (pin "1") (pinfunction "1_1") (pintype "passive"))
      (node (ref "C38") (pin "2") (pinfunction "2_2") (pintype "passive"))
      (node (ref "C4") (pin "2") (pinfunction "2_2") (pintype "passive"))
      (node (ref "C40") (pin "1") (pinfunction "1_1") (pintype "passive"))
      (node (ref "C41") (pin "1") (pinfunction "1_1") (pintype "passive"))
      (node (ref "C5") (pin "1") (pinfunction "1_1") (pintype "passive"))
      (node (ref "C6") (pin "1") (pinfunction "1_1") (pintype "passive"))
      (node (ref "C7") (pin "1") (pinfunction "1_1") (pintype "passive"))
      (node (ref "C8") (pin "1") (pinfunction "1_1") (pintype "passive"))
      (node (ref "C9") (pin "2") (pinfunction "2_2") (pintype "passive"))
      (node (ref "E1") (pin "2") (pinfunction "2_2") (pintype "passive"))
      (node (ref "IC1") (pin "1") (pinfunction "GND_1") (pintype "passive"))
      (node (ref "IC2") (pin "1") (pinfunction "GND_1") (pintype "passive"))
      (node (ref "IC3") (pin "1") (pinfunction "GND_1") (pintype "passive"))
      (node (ref "IC4") (pin "1") (pinfunction "GND_1") (pintype "passive"))
      (node (ref "IC5") (pin "1") (pinfunction "GND_1") (pintype "passive"))
      (node (ref "IC6") (pin "1") (pinfunction "GND_1") (pintype "passive"))
      (node (ref "IC7") (pin "1") (pinfunction "GND_1") (pintype "passive"))
      (node (ref "IC8") (pin "1") (pinfunction "GND_1") (pintype "passive"))
      (node (ref "JP1") (pin "10") (pinfunction "10_10") (pintype "passive"))
      (node (ref "LED1") (pin "2") (pinfunction "K_2") (pintype "passive"))
      (node (ref "R1") (pin "2") (pinfunction "2_2") (pintype "passive"))
      (node (ref "R10") (pin "1") (pinfunction "1_1") (pintype "passive"))
      (node (ref "R13") (pin "1") (pinfunction "1_1") (pintype "passive"))
      (node (ref "R14") (pin "1") (pinfunction "1_1") (pintype "passive"))
      (node (ref "R17") (pin "1") (pinfunction "1_1") (pintype "passive"))
      (node (ref "R18") (pin "1") (pinfunction "1_1") (pintype "passive"))
      (node (ref "R21") (pin "1") (pinfunction "1_1") (pintype "passive"))
      (node (ref "R22") (pin "1") (pinfunction "1_1") (pintype "passive"))
      (node (ref "R25") (pin "1") (pinfunction "1_1") (pintype "passive"))
      (node (ref "R26") (pin "1") (pinfunction "1_1") (pintype "passive"))
      (node (ref "R29") (pin "1") (pinfunction "1_1") (pintype "passive"))
      (node (ref "R30") (pin "1") (pinfunction "1_1") (pintype "passive"))
      (node (ref "R33") (pin "1") (pinfunction "1_1") (pintype "passive"))
      (node (ref "R34") (pin "1") (pinfunction "1_1") (pintype "passive"))
      (node (ref "R5") (pin "1") (pinfunction "1_1") (pintype "passive"))
      (node (ref "R6") (pin "1") (pinfunction "1_1") (pintype "passive"))
      (node (ref "R9") (pin "1") (pinfunction "1_1") (pintype "passive"))
      (node (ref "SP1") (pin "1") (pinfunction "1_1") (pintype "passive"))
      (node (ref "SP2") (pin "1") (pinfunction "1_1") (pintype "passive"))
      (node (ref "SP3") (pin "1") (pinfunction "1_1") (pintype "passive"))
      (node (ref "SP4") (pin "1") (pinfunction "1_1") (pintype "passive"))
      (node (ref "T1") (pin "2") (pinfunction "GND_2") (pintype "passive"))
      (node (ref "T2") (pin "2") (pinfunction "GND_2") (pintype "passive"))
    )
    (net (code "19") (name "Net-(D1-A)") (class "Default")
      (node (ref "D1") (pin "1") (pinfunction "A_1") (pintype "passive"))
      (node (ref "Q1") (pin "1") (pinfunction "G_1") (pintype "passive"))
      (node (ref "R1") (pin "1") (pinfunction "1_1") (pintype "passive"))
    )
    (net (code "20") (name "Net-(D1-K)") (class "Default")
      (node (ref "D1") (pin "2") (pinfunction "K_2") (pintype "passive"))
      (node (ref "Q1") (pin "2") (pinfunction "D_2") (pintype "passive"))
      (node (ref "S1") (pin "3") (pinfunction "3_3") (pintype "passive"))
    )
    (net (code "21") (name "Net-(IC1-IN)") (class "Default")
      (node (ref "IC1") (pin "2") (pinfunction "IN_2") (pintype "passive"))
      (node (ref "R3") (pin "2") (pinfunction "2_2") (pintype "passive"))
    )
    (net (code "22") (name "Net-(IC1-INH)") (class "Default")
      (node (ref "IC1") (pin "3") (pinfunction "INH_3") (pintype "passive"))
      (node (ref "R4") (pin "2") (pinfunction "2_2") (pintype "passive"))
    )
    (net (code "23") (name "Net-(IC1-IS)") (class "Default")
      (node (ref "C5") (pin "2") (pinfunction "2_2") (pintype "passive"))
      (node (ref "IC1") (pin "6") (pinfunction "IS_6") (pintype "passive"))
      (node (ref "R5") (pin "2") (pinfunction "2_2") (pintype "passive"))
    )
    (net (code "24") (name "Net-(IC1-SR)") (class "Default")
      (node (ref "C6") (pin "2") (pinfunction "2_2") (pintype "passive"))
      (node (ref "IC1") (pin "5") (pinfunction "SR_5") (pintype "passive"))
      (node (ref "R6") (pin "2") (pinfunction "2_2") (pintype "passive"))
    )
    (net (code "25") (name "Net-(IC2-IN)") (class "Default")
      (node (ref "IC2") (pin "2") (pinfunction "IN_2") (pintype "passive"))
      (node (ref "R7") (pin "2") (pinfunction "2_2") (pintype "passive"))
    )
    (net (code "26") (name "Net-(IC2-INH)") (class "Default")
      (node (ref "IC2") (pin "3") (pinfunction "INH_3") (pintype "passive"))
      (node (ref "R8") (pin "2") (pinfunction "2_2") (pintype "passive"))
    )
    (net (code "27") (name "Net-(IC2-IS)") (class "Default")
      (node (ref "C8") (pin "2") (pinfunction "2_2") (pintype "passive"))
      (node (ref "IC2") (pin "6") (pinfunction "IS_6") (pintype "passive"))
      (node (ref "R9") (pin "2") (pinfunction "2_2") (pintype "passive"))
    )
    (net (code "28") (name "Net-(IC2-SR)") (class "Default")
      (node (ref "C11") (pin "2") (pinfunction "2_2") (pintype "passive"))
      (node (ref "IC2") (pin "5") (pinfunction "SR_5") (pintype "passive"))
      (node (ref "R10") (pin "2") (pinfunction "2_2") (pintype "passive"))
    )
    (net (code "29") (name "Net-(IC3-IN)") (class "Default")
      (node (ref "IC3") (pin "2") (pinfunction "IN_2") (pintype "passive"))
      (node (ref "R11") (pin "2") (pinfunction "2_2") (pintype "passive"))
    )
    (net (code "30") (name "Net-(IC3-INH)") (class "Default")
      (node (ref "IC3") (pin "3") (pinfunction "INH_3") (pintype "passive"))
      (node (ref "R12") (pin "2") (pinfunction "2_2") (pintype "passive"))
    )
    (net (code "31") (name "Net-(IC3-IS)") (class "Default")
      (node (ref "C15") (pin "2") (pinfunction "2_2") (pintype "passive"))
      (node (ref "IC3") (pin "6") (pinfunction "IS_6") (pintype "passive"))
      (node (ref "R13") (pin "2") (pinfunction "2_2") (pintype "passive"))
    )
    (net (code "32") (name "Net-(IC3-SR)") (class "Default")
      (node (ref "C16") (pin "2") (pinfunction "2_2") (pintype "passive"))
      (node (ref "IC3") (pin "5") (pinfunction "SR_5") (pintype "passive"))
      (node (ref "R14") (pin "2") (pinfunction "2_2") (pintype "passive"))
    )
    (net (code "33") (name "Net-(IC4-IN)") (class "Default")
      (node (ref "IC4") (pin "2") (pinfunction "IN_2") (pintype "passive"))
      (node (ref "R15") (pin "2") (pinfunction "2_2") (pintype "passive"))
    )
    (net (code "34") (name "Net-(IC4-INH)") (class "Default")
      (node (ref "IC4") (pin "3") (pinfunction "INH_3") (pintype "passive"))
      (node (ref "R16") (pin "2") (pinfunction "2_2") (pintype "passive"))
    )
    (net (code "35") (name "Net-(IC4-IS)") (class "Default")
      (node (ref "C20") (pin "2") (pinfunction "2_2") (pintype "passive"))
      (node (ref "IC4") (pin "6") (pinfunction "IS_6") (pintype "passive"))
      (node (ref "R17") (pin "2") (pinfunction "2_2") (pintype "passive"))
    )
    (net (code "36") (name "Net-(IC4-SR)") (class "Default")
      (node (ref "C21") (pin "2") (pinfunction "2_2") (pintype "passive"))
      (node (ref "IC4") (pin "5") (pinfunction "SR_5") (pintype "passive"))
      (node (ref "R18") (pin "2") (pinfunction "2_2") (pintype "passive"))
    )
    (net (code "37") (name "Net-(IC5-IN)") (class "Default")
      (node (ref "IC5") (pin "2") (pinfunction "IN_2") (pintype "passive"))
      (node (ref "R19") (pin "2") (pinfunction "2_2") (pintype "passive"))
    )
    (net (code "38") (name "Net-(IC5-INH)") (class "Default")
      (node (ref "IC5") (pin "3") (pinfunction "INH_3") (pintype "passive"))
      (node (ref "R20") (pin "2") (pinfunction "2_2") (pintype "passive"))
    )
    (net (code "39") (name "Net-(IC5-IS)") (class "Default")
      (node (ref "C25") (pin "2") (pinfunction "2_2") (pintype "passive"))
      (node (ref "IC5") (pin "6") (pinfunction "IS_6") (pintype "passive"))
      (node (ref "R21") (pin "2") (pinfunction "2_2") (pintype "passive"))
    )
    (net (code "40") (name "Net-(IC5-SR)") (class "Default")
      (node (ref "C26") (pin "2") (pinfunction "2_2") (pintype "passive"))
      (node (ref "IC5") (pin "5") (pinfunction "SR_5") (pintype "passive"))
      (node (ref "R22") (pin "2") (pinfunction "2_2") (pintype "passive"))
    )
    (net (code "41") (name "Net-(IC6-IN)") (class "Default")
      (node (ref "IC6") (pin "2") (pinfunction "IN_2") (pintype "passive"))
      (node (ref "R23") (pin "2") (pinfunction "2_2") (pintype "passive"))
    )
    (net (code "42") (name "Net-(IC6-INH)") (class "Default")
      (node (ref "IC6") (pin "3") (pinfunction "INH_3") (pintype "passive"))
      (node (ref "R24") (pin "2") (pinfunction "2_2") (pintype "passive"))
    )
    (net (code "43") (name "Net-(IC6-IS)") (class "Default")
      (node (ref "C30") (pin "2") (pinfunction "2_2") (pintype "passive"))
      (node (ref "IC6") (pin "6") (pinfunction "IS_6") (pintype "passive"))
      (node (ref "R25") (pin "2") (pinfunction "2_2") (pintype "passive"))
    )
    (net (code "44") (name "Net-(IC6-SR)") (class "Default")
      (node (ref "C31") (pin "2") (pinfunction "2_2") (pintype "passive"))
      (node (ref "IC6") (pin "5") (pinfunction "SR_5") (pintype "passive"))
      (node (ref "R26") (pin "2") (pinfunction "2_2") (pintype "passive"))
    )
    (net (code "45") (name "Net-(IC7-IN)") (class "Default")
      (node (ref "IC7") (pin "2") (pinfunction "IN_2") (pintype "passive"))
      (node (ref "R27") (pin "2") (pinfunction "2_2") (pintype "passive"))
    )
    (net (code "46") (name "Net-(IC7-INH)") (class "Default")
      (node (ref "IC7") (pin "3") (pinfunction "INH_3") (pintype "passive"))
      (node (ref "R28") (pin "2") (pinfunction "2_2") (pintype "passive"))
    )
    (net (code "47") (name "Net-(IC7-IS)") (class "Default")
      (node (ref "C35") (pin "2") (pinfunction "2_2") (pintype "passive"))
      (node (ref "IC7") (pin "6") (pinfunction "IS_6") (pintype "passive"))
      (node (ref "R29") (pin "2") (pinfunction "2_2") (pintype "passive"))
    )
    (net (code "48") (name "Net-(IC7-SR)") (class "Default")
      (node (ref "C36") (pin "2") (pinfunction "2_2") (pintype "passive"))
      (node (ref "IC7") (pin "5") (pinfunction "SR_5") (pintype "passive"))
      (node (ref "R30") (pin "2") (pinfunction "2_2") (pintype "passive"))
    )
    (net (code "49") (name "Net-(IC8-IN)") (class "Default")
      (node (ref "IC8") (pin "2") (pinfunction "IN_2") (pintype "passive"))
      (node (ref "R31") (pin "2") (pinfunction "2_2") (pintype "passive"))
    )
    (net (code "50") (name "Net-(IC8-INH)") (class "Default")
      (node (ref "IC8") (pin "3") (pinfunction "INH_3") (pintype "passive"))
      (node (ref "R32") (pin "2") (pinfunction "2_2") (pintype "passive"))
    )
    (net (code "51") (name "Net-(IC8-IS)") (class "Default")
      (node (ref "C40") (pin "2") (pinfunction "2_2") (pintype "passive"))
      (node (ref "IC8") (pin "6") (pinfunction "IS_6") (pintype "passive"))
      (node (ref "R33") (pin "2") (pinfunction "2_2") (pintype "passive"))
    )
    (net (code "52") (name "Net-(IC8-SR)") (class "Default")
      (node (ref "C41") (pin "2") (pinfunction "2_2") (pintype "passive"))
      (node (ref "IC8") (pin "5") (pinfunction "SR_5") (pintype "passive"))
      (node (ref "R34") (pin "2") (pinfunction "2_2") (pintype "passive"))
    )
    (net (code "53") (name "Net-(LED1-A)") (class "Default")
      (node (ref "LED1") (pin "1") (pinfunction "A_1") (pintype "passive"))
      (node (ref "R2") (pin "2") (pinfunction "2_2") (pintype "passive"))
    )
    (net (code "54") (name "Net-(LED2-A)") (class "Default")
      (node (ref "LED2") (pin "1") (pinfunction "A_1") (pintype "passive"))
      (node (ref "LED3") (pin "2") (pinfunction "K_2") (pintype "passive"))
      (node (ref "R35") (pin "2") (pinfunction "2_2") (pintype "passive"))
    )
    (net (code "55") (name "Net-(LED4-A)") (class "Default")
      (node (ref "LED4") (pin "1") (pinfunction "A_1") (pintype "passive"))
      (node (ref "LED5") (pin "2") (pinfunction "K_2") (pintype "passive"))
      (node (ref "R36") (pin "2") (pinfunction "2_2") (pintype "passive"))
    )
    (net (code "56") (name "Net-(LED6-A)") (class "Default")
      (node (ref "LED6") (pin "1") (pinfunction "A_1") (pintype "passive"))
      (node (ref "LED7") (pin "2") (pinfunction "K_2") (pintype "passive"))
      (node (ref "R37") (pin "2") (pinfunction "2_2") (pintype "passive"))
    )
    (net (code "57") (name "Net-(LED8-A)") (class "Default")
      (node (ref "LED8") (pin "1") (pinfunction "A_1") (pintype "passive"))
      (node (ref "LED9") (pin "2") (pinfunction "K_2") (pintype "passive"))
      (node (ref "R38") (pin "2") (pinfunction "2_2") (pintype "passive"))
    )
    (net (code "58") (name "Net-(T1-VCC)") (class "Default")
      (node (ref "S1") (pin "1") (pinfunction "1_1") (pintype "passive"))
      (node (ref "S1") (pin "2") (pinfunction "2_2") (pintype "passive"))
      (node (ref "T1") (pin "1") (pinfunction "VCC_1") (pintype "passive"))
    )
    (net (code "59") (name "Net-(T2-VCC)") (class "Default")
      (node (ref "S2") (pin "1") (pinfunction "1_1") (pintype "passive"))
      (node (ref "T2") (pin "1") (pinfunction "VCC_1") (pintype "passive"))
    )
    (net (code "60") (name "VCC") (class "Default")
      (node (ref "C1") (pin "1") (pinfunction "1_1") (pintype "passive"))
      (node (ref "C10") (pin "2") (pinfunction "2_2") (pintype "passive"))
      (node (ref "C12") (pin "2") (pinfunction "2_2") (pintype "passive"))
      (node (ref "C14") (pin "2") (pinfunction "2_2") (pintype "passive"))
      (node (ref "C17") (pin "2") (pinfunction "2_2") (pintype "passive"))
      (node (ref "C19") (pin "2") (pinfunction "2_2") (pintype "passive"))
      (node (ref "C2") (pin "2") (pinfunction "2_2") (pintype "passive"))
      (node (ref "C22") (pin "2") (pinfunction "2_2") (pintype "passive"))
      (node (ref "C24") (pin "2") (pinfunction "2_2") (pintype "passive"))
      (node (ref "C27") (pin "2") (pinfunction "2_2") (pintype "passive"))
      (node (ref "C29") (pin "2") (pinfunction "2_2") (pintype "passive"))
      (node (ref "C3") (pin "2") (pinfunction "2_2") (pintype "passive"))
      (node (ref "C32") (pin "2") (pinfunction "2_2") (pintype "passive"))
      (node (ref "C34") (pin "2") (pinfunction "2_2") (pintype "passive"))
      (node (ref "C37") (pin "2") (pinfunction "2_2") (pintype "passive"))
      (node (ref "C39") (pin "2") (pinfunction "2_2") (pintype "passive"))
      (node (ref "C7") (pin "2") (pinfunction "2_2") (pintype "passive"))
      (node (ref "E1") (pin "1") (pinfunction "1_1") (pintype "passive"))
      (node (ref "IC1") (pin "7") (pinfunction "VS_7") (pintype "passive"))
      (node (ref "IC2") (pin "7") (pinfunction "VS_7") (pintype "passive"))
      (node (ref "IC3") (pin "7") (pinfunction "VS_7") (pintype "passive"))
      (node (ref "IC4") (pin "7") (pinfunction "VS_7") (pintype "passive"))
      (node (ref "IC5") (pin "7") (pinfunction "VS_7") (pintype "passive"))
      (node (ref "IC6") (pin "7") (pinfunction "VS_7") (pintype "passive"))
      (node (ref "IC7") (pin "7") (pinfunction "VS_7") (pintype "passive"))
      (node (ref "IC8") (pin "7") (pinfunction "VS_7") (pintype "passive"))
      (node (ref "Q1") (pin "3") (pinfunction "S_3") (pintype "passive"))
      (node (ref "R2") (pin "1") (pinfunction "1_1") (pintype "passive"))
      (node (ref "S2") (pin "2") (pinfunction "2_2") (pintype "passive"))
      (node (ref "S2") (pin "3") (pinfunction "3_3") (pintype "passive"))
    )
  )
)
